# 1_Interface.net
KiCad netlist of a schematic drawn in Altium Designer
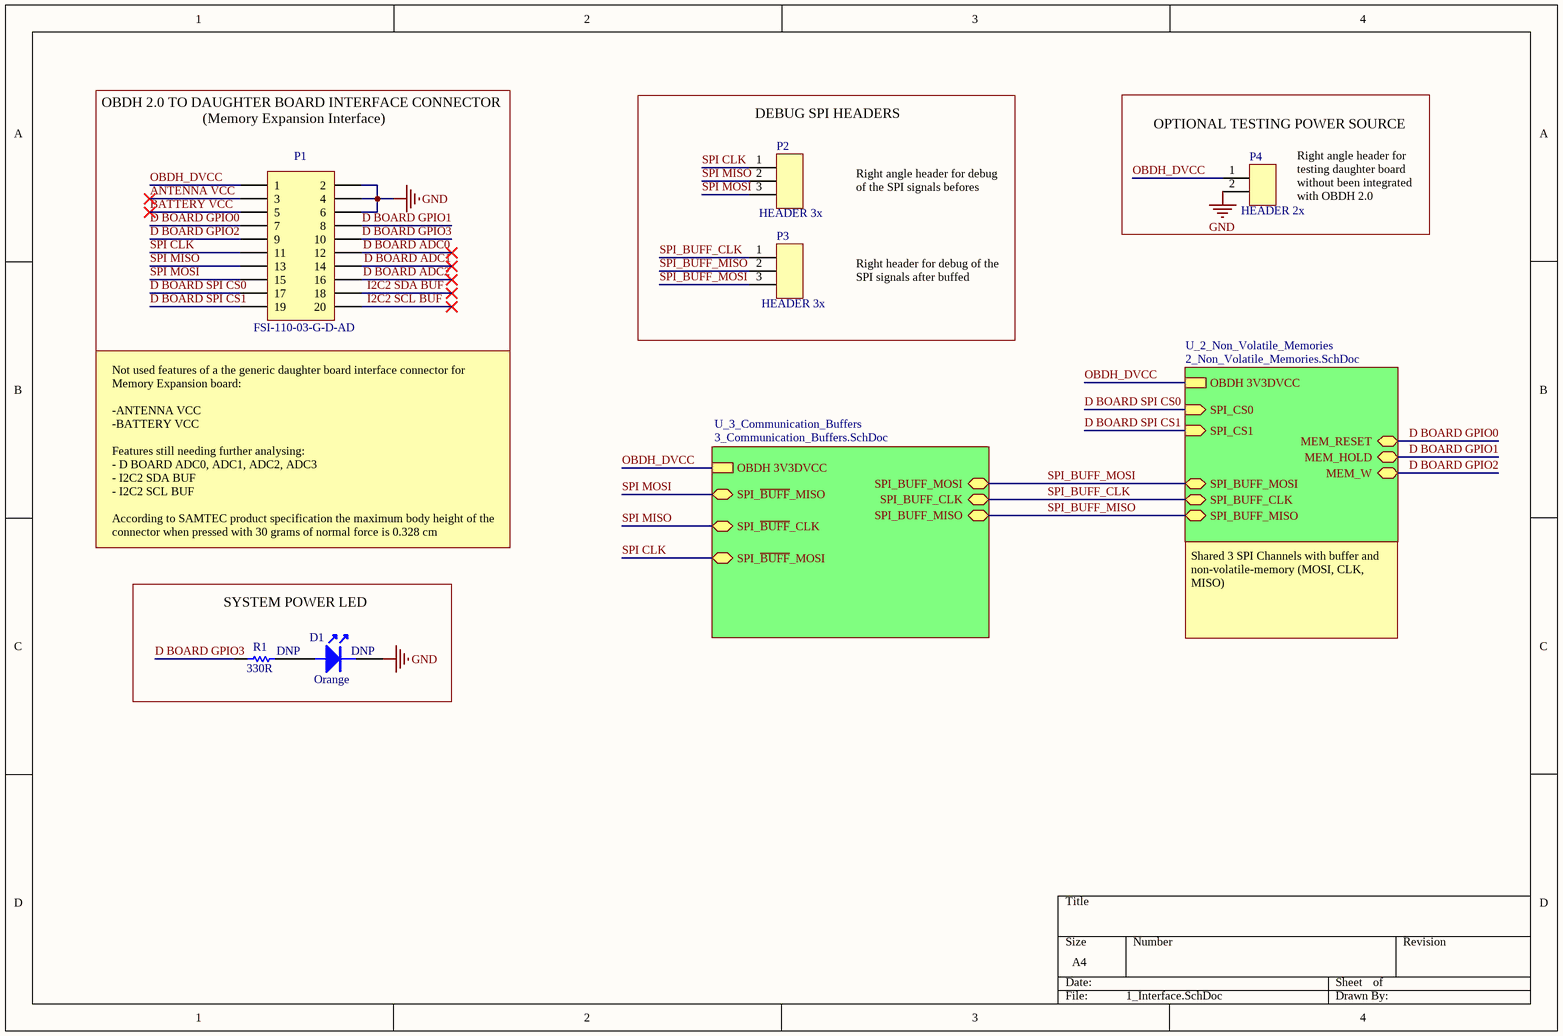
[diagram p0: 1_Interface.SchDoc]

(export (version "E")
  (design (tool "Eeschema 10.0.6"))
  (components
    (comp (ref "D1")
      (value "Orange")
      (footprint "0805-LED")
      (description "SMD Orange LED")
      (fields (field (name "PARTNUMBER") "LTST-C170KFKT"))
      (libsource (lib "OBDH_Eng_Model_2_ALT") (part "LED/R_0603"))
    )
    (comp (ref "P1")
      (value "FSI-110-03-G-D-AD")
      (footprint "Mating FSI-110-03-G-D-AD")
      (libsource (lib "Memory_Expansion_Daughter_Board_SchLib") (part "FSI-110-03-G-D-AD"))
    )
    (comp (ref "P2")
      (value "HEADER 3x")
      (footprint "Header1x3")
      (description "Conn Unshrouded Header HDR 3 POS 2.54mm Solder RA Thru-Hole Automotive Bulk")
      (fields
        (field (name "MANUFACTURER") "Samtec")
        (field (name "MANUFACTURER PART NUMBER") "TSW-103-08-G-S-RA")
      )
      (libsource (lib "Memory_Expansion_Daughter_Board_SchLib") (part "TSW-103-08-G-S-RA"))
    )
    (comp (ref "P3")
      (value "HEADER 3x")
      (footprint "Header1x3")
      (description "Conn Unshrouded Header HDR 3 POS 2.54mm Solder RA Thru-Hole Automotive Bulk")
      (fields
        (field (name "MANUFACTURER") "Samtec")
        (field (name "MANUFACTURER PART NUMBER") "TSW-103-08-G-S-RA")
      )
      (libsource (lib "Memory_Expansion_Daughter_Board_SchLib") (part "TSW-103-08-G-S-RA"))
    )
    (comp (ref "P4")
      (value "HEADER 2x")
      (footprint "HDR 1X2")
      (description "Conn Unshrouded Header HDR 2 POS 2.54mm Solder RA Thru-Hole Automotive Bulk")
      (fields
        (field (name "MANUFACTURER") "Samtec")
        (field (name "MANUFACTURER PART NUMBER") "TSW-102-08-G-S-RA")
      )
      (libsource (lib "Memory_Expansion_Daughter_Board_SchLib") (part "HEADER 2x"))
    )
    (comp (ref "R1")
      (value "330R")
      (footprint "0805")
      (description "RES 330R OHM 1/4W 1% 0805")
      (fields (field (name "PARTNUMBER") "RC0805FR-07330RL"))
      (libsource (lib "Memory_Expansion_Daughter_Board_SchLib") (part "R330R_1%_1/4W_0805"))
    )
  )
  (nets
    (net (code "1") (name "/ANTENNA VCC") (class "Default")
      (node (ref "P1") (pin "3") (pinfunction "3_3") (pintype "passive+no_connect"))
    )
    (net (code "2") (name "/BATTERY VCC") (class "Default")
      (node (ref "P1") (pin "5") (pinfunction "5_5") (pintype "passive+no_connect"))
    )
    (net (code "3") (name "/D BOARD ADC0") (class "Default")
      (node (ref "P1") (pin "12") (pinfunction "12_12") (pintype "passive+no_connect"))
    )
    (net (code "4") (name "/D BOARD ADC1") (class "Default")
      (node (ref "P1") (pin "14") (pinfunction "14_14") (pintype "passive+no_connect"))
    )
    (net (code "5") (name "/D BOARD ADC2") (class "Default")
      (node (ref "P1") (pin "16") (pinfunction "16_16") (pintype "passive+no_connect"))
    )
    (net (code "6") (name "/D BOARD GPIO0") (class "Default")
      (node (ref "P1") (pin "7") (pinfunction "7_7") (pintype "passive"))
    )
    (net (code "7") (name "/D BOARD GPIO1") (class "Default")
      (node (ref "P1") (pin "8") (pinfunction "8_8") (pintype "passive"))
    )
    (net (code "8") (name "/D BOARD GPIO2") (class "Default")
      (node (ref "P1") (pin "9") (pinfunction "9_9") (pintype "passive"))
    )
    (net (code "9") (name "/D BOARD GPIO3") (class "Default")
      (node (ref "P1") (pin "10") (pinfunction "10_10") (pintype "passive"))
      (node (ref "R1") (pin "1") (pinfunction "1_1") (pintype "passive"))
    )
    (net (code "10") (name "/D BOARD SPI CS0") (class "Default")
      (node (ref "P1") (pin "17") (pinfunction "17_17") (pintype "passive"))
    )
    (net (code "11") (name "/D BOARD SPI CS1") (class "Default")
      (node (ref "P1") (pin "19") (pinfunction "19_19") (pintype "passive"))
    )
    (net (code "12") (name "/I2C2 SCL BUF") (class "Default")
      (node (ref "P1") (pin "20") (pinfunction "20_20") (pintype "passive+no_connect"))
    )
    (net (code "13") (name "/I2C2 SDA BUF") (class "Default")
      (node (ref "P1") (pin "18") (pinfunction "18_18") (pintype "passive+no_connect"))
    )
    (net (code "14") (name "/OBDH_DVCC") (class "Default")
      (node (ref "P1") (pin "1") (pinfunction "1_1") (pintype "passive"))
      (node (ref "P4") (pin "1") (pintype "passive"))
    )
    (net (code "15") (name "/SPI CLK") (class "Default")
      (node (ref "P1") (pin "11") (pinfunction "11_11") (pintype "passive"))
      (node (ref "P2") (pin "1") (pintype "passive"))
    )
    (net (code "16") (name "/SPI MISO") (class "Default")
      (node (ref "P1") (pin "13") (pinfunction "13_13") (pintype "passive"))
      (node (ref "P2") (pin "2") (pintype "passive"))
    )
    (net (code "17") (name "/SPI MOSI") (class "Default")
      (node (ref "P1") (pin "15") (pinfunction "15_15") (pintype "passive"))
      (node (ref "P2") (pin "3") (pintype "passive"))
    )
    (net (code "18") (name "/SPI_BUFF_CLK") (class "Default") (node (ref "P3") (pin "1") (pintype "passive")))
    (net (code "20") (name "/SPI_BUFF_MISO") (class "Default")
      (node (ref "P3") (pin "2") (pintype "passive"))
    )
    (net (code "22") (name "/SPI_BUFF_MOSI") (class "Default")
      (node (ref "P3") (pin "3") (pintype "passive"))
    )
    (net (code "24") (name "GND") (class "Default")
      (node (ref "D1") (pin "2") (pinfunction "K_2") (pintype "passive"))
      (node (ref "P1") (pin "2") (pinfunction "2_2") (pintype "passive"))
      (node (ref "P1") (pin "4") (pinfunction "4_4") (pintype "passive"))
      (node (ref "P1") (pin "6") (pinfunction "6_6") (pintype "passive"))
      (node (ref "P4") (pin "2") (pintype "passive"))
    )
    (net (code "25") (name "Net-(D1-A)") (class "Default")
      (node (ref "D1") (pin "1") (pinfunction "A_1") (pintype "passive"))
      (node (ref "R1") (pin "2") (pinfunction "2_2") (pintype "passive"))
    )
  )
)
